# Temperature_Sensor_v1.net
KiCad netlist of a schematic drawn in EAGLE
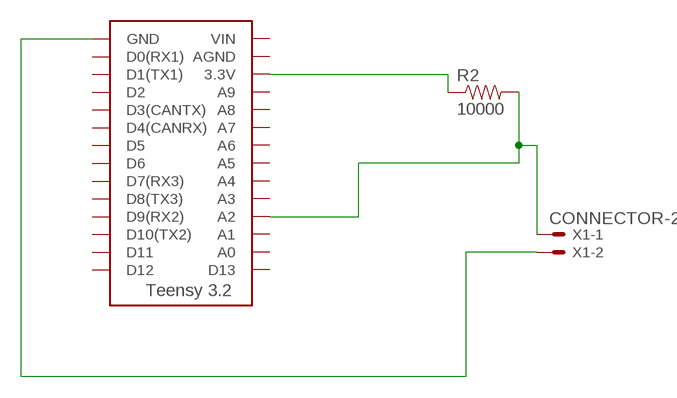
[diagram p0: schematic, sheet 1]

(export (version "E")
  (design (tool "Eeschema 10.0.6"))
  (components
    (comp (ref "R2")
      (value "10000")
      (footprint "eagle-import:AXIAL-0.5")
      (libsource (lib "eagle-import") (part "RESISTORPTH-1/2W"))
    )
    (comp (ref "U$1")
      (value "TEENSY_3.2_SIMPLE")
      (footprint "eagle-import:TEENSY_3.2_SIMPLE")
      (libsource (lib "eagle-import") (part "TEENSY_3.2_SIMPLE"))
    )
    (comp (ref "X1")
      (value "CONNECTOR-2")
      (footprint "eagle-import:MINIFIT_5566-2")
      (libsource (lib "eagle-import") (part "CONNECTOR-2"))
    )
  )
  (nets
    (net (code "1") (name "Net-(R2-1)") (class "Default")
      (node (ref "R2") (pin "P$1") (pinfunction "1_P$1") (pintype "passive"))
      (node (ref "U$1") (pin "3.3V") (pinfunction "3.3V_3.3V") (pintype "bidirectional"))
    )
    (net (code "2") (name "Net-(R2-2)") (class "Default")
      (node (ref "R2") (pin "P$2") (pinfunction "2_P$2") (pintype "passive"))
      (node (ref "U$1") (pin "A2") (pinfunction "A2_A2") (pintype "bidirectional"))
      (node (ref "X1") (pin "1") (pinfunction "S_1") (pintype "passive"))
    )
    (net (code "3") (name "Net-(X1B-S)") (class "Default")
      (node (ref "U$1") (pin "GND") (pinfunction "GND_GND") (pintype "bidirectional"))
      (node (ref "X1") (pin "2") (pinfunction "S_2") (pintype "passive"))
    )
    (net (code "4") (name "unconnected-(U$1-PadA0)") (class "Default")
      (node (ref "U$1") (pin "A0") (pinfunction "A0_A0") (pintype "bidirectional"))
    )
    (net (code "5") (name "unconnected-(U$1-PadA1)") (class "Default")
      (node (ref "U$1") (pin "A1") (pinfunction "A1_A1") (pintype "bidirectional"))
    )
    (net (code "6") (name "unconnected-(U$1-PadA3)") (class "Default")
      (node (ref "U$1") (pin "A3") (pinfunction "A3_A3") (pintype "bidirectional"))
    )
    (net (code "7") (name "unconnected-(U$1-PadA4)") (class "Default")
      (node (ref "U$1") (pin "A4") (pinfunction "A4_A4") (pintype "bidirectional"))
    )
    (net (code "8") (name "unconnected-(U$1-PadA5)") (class "Default")
      (node (ref "U$1") (pin "A5") (pinfunction "A5_A5") (pintype "bidirectional"))
    )
    (net (code "9") (name "unconnected-(U$1-PadA6)") (class "Default")
      (node (ref "U$1") (pin "A6") (pinfunction "A6_A6") (pintype "bidirectional"))
    )
    (net (code "10") (name "unconnected-(U$1-PadA7)") (class "Default")
      (node (ref "U$1") (pin "A7") (pinfunction "A7_A7") (pintype "bidirectional"))
    )
    (net (code "11") (name "unconnected-(U$1-PadA8)") (class "Default")
      (node (ref "U$1") (pin "A8") (pinfunction "A8_A8") (pintype "bidirectional"))
    )
    (net (code "12") (name "unconnected-(U$1-PadA9)") (class "Default")
      (node (ref "U$1") (pin "A9") (pinfunction "A9_A9") (pintype "bidirectional"))
    )
    (net (code "13") (name "unconnected-(U$1-PadAGND)") (class "Default")
      (node (ref "U$1") (pin "AGND") (pinfunction "AGND_AGND") (pintype "bidirectional"))
    )
    (net (code "14") (name "unconnected-(U$1-PadD0(RX1))") (class "Default")
      (node (ref "U$1") (pin "D0(RX1)") (pinfunction "D0(RX1)_D0(RX1)") (pintype "bidirectional"))
    )
    (net (code "15") (name "unconnected-(U$1-PadD1(TX1))") (class "Default")
      (node (ref "U$1") (pin "D1(TX1)") (pinfunction "D1(TX1)_D1(TX1)") (pintype "bidirectional"))
    )
    (net (code "16") (name "unconnected-(U$1-PadD2)") (class "Default")
      (node (ref "U$1") (pin "D2") (pinfunction "D2_D2") (pintype "bidirectional"))
    )
    (net (code "17") (name "unconnected-(U$1-PadD3(CANTX))") (class "Default")
      (node (ref "U$1") (pin "D3(CANTX)") (pinfunction "D3(CANTX)_D3(CANTX)") (pintype "bidirectional"))
    )
    (net (code "18") (name "unconnected-(U$1-PadD4(CANRX))") (class "Default")
      (node (ref "U$1") (pin "D4(CANRX)") (pinfunction "D4(CANRX)_D4(CANRX)") (pintype "bidirectional"))
    )
    (net (code "19") (name "unconnected-(U$1-PadD5)") (class "Default")
      (node (ref "U$1") (pin "D5") (pinfunction "D5_D5") (pintype "bidirectional"))
    )
    (net (code "20") (name "unconnected-(U$1-PadD6)") (class "Default")
      (node (ref "U$1") (pin "D6") (pinfunction "D6_D6") (pintype "bidirectional"))
    )
    (net (code "21") (name "unconnected-(U$1-PadD7(RX3))") (class "Default")
      (node (ref "U$1") (pin "D7(RX3)") (pinfunction "D7(RX3)_D7(RX3)") (pintype "bidirectional"))
    )
    (net (code "22") (name "unconnected-(U$1-PadD8(TX3))") (class "Default")
      (node (ref "U$1") (pin "D8(TX3)") (pinfunction "D8(TX3)_D8(TX3)") (pintype "bidirectional"))
    )
    (net (code "23") (name "unconnected-(U$1-PadD9(RX2))") (class "Default")
      (node (ref "U$1") (pin "D9(RX2)") (pinfunction "D9(RX2)_D9(RX2)") (pintype "bidirectional"))
    )
    (net (code "24") (name "unconnected-(U$1-PadD10(TX2))") (class "Default")
      (node (ref "U$1") (pin "D10(TX2)") (pinfunction "D10(TX2)_D10(TX2)") (pintype "bidirectional"))
    )
    (net (code "25") (name "unconnected-(U$1-PadD11)") (class "Default")
      (node (ref "U$1") (pin "D11") (pinfunction "D11_D11") (pintype "bidirectional"))
    )
    (net (code "26") (name "unconnected-(U$1-PadD12)") (class "Default")
      (node (ref "U$1") (pin "D12") (pinfunction "D12_D12") (pintype "bidirectional"))
    )
    (net (code "27") (name "unconnected-(U$1-PadD13)") (class "Default")
      (node (ref "U$1") (pin "D13") (pinfunction "D13_D13") (pintype "bidirectional"))
    )
    (net (code "28") (name "unconnected-(U$1-PadVIN)") (class "Default")
      (node (ref "U$1") (pin "VIN") (pinfunction "VIN_VIN") (pintype "bidirectional"))
    )
  )
)
